# wireless.net
KiCad netlist of a schematic drawn in Altium Designer
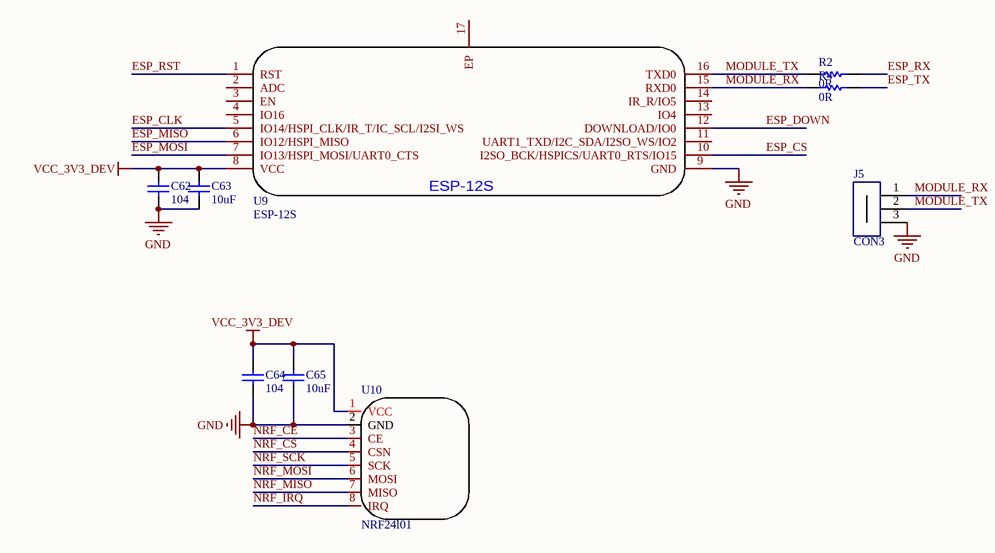
[diagram p0: wireless.SchDoc]

(export (version "E")
  (design (tool "Eeschema 10.0.6"))
  (components
    (comp (ref "C62") (value "104") (footprint "C 0603") (libsource (lib "Sheet") (part "CAP")))
    (comp (ref "C63") (value "10uF") (footprint "C 0603") (libsource (lib "Sheet") (part "CAP")))
    (comp (ref "C64") (value "104") (footprint "C 0603") (libsource (lib "Sheet") (part "CAP")))
    (comp (ref "C65") (value "10uF") (footprint "C 0603") (libsource (lib "Sheet") (part "CAP")))
    (comp (ref "J5") (value "CON3") (footprint "SMD_3P-1.25") (libsource (lib "Sheet") (part "CON3")))
    (comp (ref "R2") (value "0R") (footprint "R 0603") (libsource (lib "Sheet") (part "RES")))
    (comp (ref "R4") (value "0R") (footprint "R 0603") (libsource (lib "Sheet") (part "RES")))
    (comp (ref "U9") (value "ESP-12S") (footprint "ESP-12S") (libsource (lib "Sheet") (part "ESP-12S")))
    (comp (ref "U10") (value "NRF24l01") (footprint "NRF24l01") (libsource (lib "Sheet") (part "NRF24l01")))
  )
  (nets
    (net (code "1") (name "/ESP_CLK") (class "Default")
      (node (ref "U9") (pin "5") (pinfunction "IO14/HSPI_CLK/IR_T/IC_SCL/I2SI_WS_5") (pintype "passive"))
    )
    (net (code "2") (name "/ESP_CS") (class "Default")
      (node (ref "U9") (pin "10") (pinfunction "I2SO_BCK/HSPICS/UART0_RTS/IO15_10") (pintype "passive"))
    )
    (net (code "3") (name "/ESP_DOWN") (class "Default")
      (node (ref "U9") (pin "12") (pinfunction "DOWNLOAD/IO0_12") (pintype "passive"))
    )
    (net (code "4") (name "/ESP_MISO") (class "Default")
      (node (ref "U9") (pin "6") (pinfunction "IO12/HSPI_MISO_6") (pintype "passive"))
    )
    (net (code "5") (name "/ESP_MOSI") (class "Default")
      (node (ref "U9") (pin "7") (pinfunction "IO13/HSPI_MOSI/UART0_CTS_7") (pintype "passive"))
    )
    (net (code "6") (name "/ESP_RST") (class "Default")
      (node (ref "U9") (pin "1") (pinfunction "RST_1") (pintype "passive"))
    )
    (net (code "7") (name "/ESP_RX") (class "Default")
      (node (ref "R2") (pin "2") (pinfunction "2_2") (pintype "passive"))
    )
    (net (code "8") (name "/ESP_TX") (class "Default")
      (node (ref "R4") (pin "2") (pinfunction "2_2") (pintype "passive"))
    )
    (net (code "9") (name "/MODULE_RX") (class "Default")
      (node (ref "J5") (pin "1") (pinfunction "1_1") (pintype "passive"))
      (node (ref "R4") (pin "1") (pinfunction "1_1") (pintype "passive"))
      (node (ref "U9") (pin "15") (pinfunction "RXD0_15") (pintype "passive"))
    )
    (net (code "10") (name "/MODULE_TX") (class "Default")
      (node (ref "J5") (pin "2") (pinfunction "2_2") (pintype "passive"))
      (node (ref "R2") (pin "1") (pinfunction "1_1") (pintype "passive"))
      (node (ref "U9") (pin "16") (pinfunction "TXD0_16") (pintype "passive"))
    )
    (net (code "11") (name "/NRF_CE") (class "Default")
      (node (ref "U10") (pin "3") (pinfunction "CE_3") (pintype "passive"))
    )
    (net (code "12") (name "/NRF_CS") (class "Default")
      (node (ref "U10") (pin "4") (pinfunction "CSN_4") (pintype "passive"))
    )
    (net (code "13") (name "/NRF_IRQ") (class "Default")
      (node (ref "U10") (pin "8") (pinfunction "IRQ_8") (pintype "passive"))
    )
    (net (code "14") (name "/NRF_MISO") (class "Default")
      (node (ref "U10") (pin "7") (pinfunction "MISO_7") (pintype "passive"))
    )
    (net (code "15") (name "/NRF_MOSI") (class "Default")
      (node (ref "U10") (pin "6") (pinfunction "MOSI_6") (pintype "passive"))
    )
    (net (code "16") (name "/NRF_SCK") (class "Default")
      (node (ref "U10") (pin "5") (pinfunction "SCK_5") (pintype "passive"))
    )
    (net (code "17") (name "GND") (class "Default")
      (node (ref "C62") (pin "2") (pinfunction "2_2") (pintype "passive"))
      (node (ref "C63") (pin "2") (pinfunction "2_2") (pintype "passive"))
      (node (ref "C64") (pin "2") (pinfunction "2_2") (pintype "passive"))
      (node (ref "C65") (pin "2") (pinfunction "2_2") (pintype "passive"))
      (node (ref "J5") (pin "3") (pinfunction "3_3") (pintype "passive"))
      (node (ref "U10") (pin "2") (pinfunction "GND_2") (pintype "passive"))
      (node (ref "U9") (pin "9") (pinfunction "GND_9") (pintype "passive"))
    )
    (net (code "18") (name "VCC_3V3_DEV") (class "Default")
      (node (ref "C62") (pin "1") (pinfunction "1_1") (pintype "passive"))
      (node (ref "C63") (pin "1") (pinfunction "1_1") (pintype "passive"))
      (node (ref "C64") (pin "1") (pinfunction "1_1") (pintype "passive"))
      (node (ref "C65") (pin "1") (pinfunction "1_1") (pintype "passive"))
      (node (ref "U10") (pin "1") (pinfunction "VCC_1") (pintype "passive"))
      (node (ref "U9") (pin "8") (pinfunction "VCC_8") (pintype "passive"))
    )
    (net (code "19") (name "unconnected-(U9-ADC-Pad2)") (class "Default")
      (node (ref "U9") (pin "2") (pinfunction "ADC_2") (pintype "passive"))
    )
    (net (code "20") (name "unconnected-(U9-EN-Pad3)") (class "Default")
      (node (ref "U9") (pin "3") (pinfunction "EN_3") (pintype "passive"))
    )
    (net (code "21") (name "unconnected-(U9-EP-Pad17)") (class "Default")
      (node (ref "U9") (pin "17") (pinfunction "EP_17") (pintype "passive"))
    )
    (net (code "22") (name "unconnected-(U9-IO4-Pad13)") (class "Default")
      (node (ref "U9") (pin "13") (pinfunction "IO4_13") (pintype "passive"))
    )
    (net (code "23") (name "unconnected-(U9-IO16-Pad4)") (class "Default")
      (node (ref "U9") (pin "4") (pinfunction "IO16_4") (pintype "passive"))
    )
    (net (code "24") (name "unconnected-(U9-IR_R{slash}IO5-Pad14)") (class "Default")
      (node (ref "U9") (pin "14") (pinfunction "IR_R/IO5_14") (pintype "passive"))
    )
    (net (code "25") (name "unconnected-(U9-UART1_TXD{slash}I2C_SDA{slash}I2SO_WS{slash}IO2-Pad11)") (class "Default")
      (node (ref "U9") (pin "11") (pinfunction "UART1_TXD/I2C_SDA/I2SO_WS/IO2_11") (pintype "passive"))
    )
  )
)
